# sanwa-obsf-30.net
KiCad netlist of a schematic drawn in EAGLE
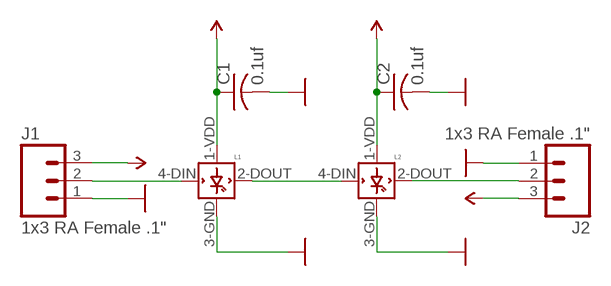
[diagram p0: schematic, sheet 1]

(export (version "E")
  (design (tool "Eeschema 10.0.6"))
  (components
    (comp (ref "C1")
      (value "0.1uf")
      (footprint "eagle-import:C0603K")
      (libsource (lib "eagle-import") (part "C-USC0603K"))
    )
    (comp (ref "C2")
      (value "0.1uf")
      (footprint "eagle-import:C0603K")
      (libsource (lib "eagle-import") (part "C-USC0603K"))
    )
    (comp (ref "J1")
      (value "1x3 RA Female .1\"")
      (footprint "eagle-import:JST-3-PTH-VERT")
      (libsource (lib "eagle-import") (part "M03JST-PTH-VERT"))
    )
    (comp (ref "J2")
      (value "1x3 RA Female .1\"")
      (footprint "eagle-import:JST-3-PTH-VERT")
      (libsource (lib "eagle-import") (part "M03JST-PTH-VERT"))
    )
    (comp (ref "L1")
      (value "WS2812B")
      (footprint "eagle-import:WS2812B")
      (libsource (lib "eagle-import") (part "WS2812B"))
    )
    (comp (ref "L2")
      (value "WS2812B")
      (footprint "eagle-import:WS2812B")
      (libsource (lib "eagle-import") (part "WS2812B"))
    )
  )
  (nets
    (net (code "1") (name "GND") (class "Default")
      (node (ref "C1") (pin "2") (pinfunction "2_2") (pintype "passive"))
      (node (ref "C2") (pin "2") (pinfunction "2_2") (pintype "passive"))
      (node (ref "J1") (pin "1") (pinfunction "1_1") (pintype "passive"))
      (node (ref "J2") (pin "1") (pinfunction "1_1") (pintype "passive"))
      (node (ref "L1") (pin "3-GND") (pinfunction "GND_3-GND") (pintype "bidirectional"))
      (node (ref "L2") (pin "3-GND") (pinfunction "GND_3-GND") (pintype "bidirectional"))
    )
    (net (code "2") (name "Net-(L1-DIN)") (class "Default")
      (node (ref "J1") (pin "2") (pinfunction "2_2") (pintype "passive"))
      (node (ref "L1") (pin "4-DIN") (pinfunction "DIN_4-DIN") (pintype "input"))
    )
    (net (code "3") (name "Net-(L1-DOUT)") (class "Default")
      (node (ref "L1") (pin "2-DOUT") (pinfunction "DOUT_2-DOUT") (pintype "output"))
      (node (ref "L2") (pin "4-DIN") (pinfunction "DIN_4-DIN") (pintype "input"))
    )
    (net (code "4") (name "Net-(L2-DOUT)") (class "Default")
      (node (ref "J2") (pin "2") (pinfunction "2_2") (pintype "passive"))
      (node (ref "L2") (pin "2-DOUT") (pinfunction "DOUT_2-DOUT") (pintype "output"))
    )
    (net (code "5") (name "VCC") (class "Default")
      (node (ref "C1") (pin "1") (pinfunction "1_1") (pintype "passive"))
      (node (ref "C2") (pin "1") (pinfunction "1_1") (pintype "passive"))
      (node (ref "J1") (pin "3") (pinfunction "3_3") (pintype "passive"))
      (node (ref "J2") (pin "3") (pinfunction "3_3") (pintype "passive"))
      (node (ref "L1") (pin "1-VDD") (pinfunction "VDD_1-VDD") (pintype "bidirectional"))
      (node (ref "L2") (pin "1-VDD") (pinfunction "VDD_1-VDD") (pintype "bidirectional"))
    )
  )
)
